# met_breadboard.net
KiCad netlist of a schematic drawn in Altium Designer
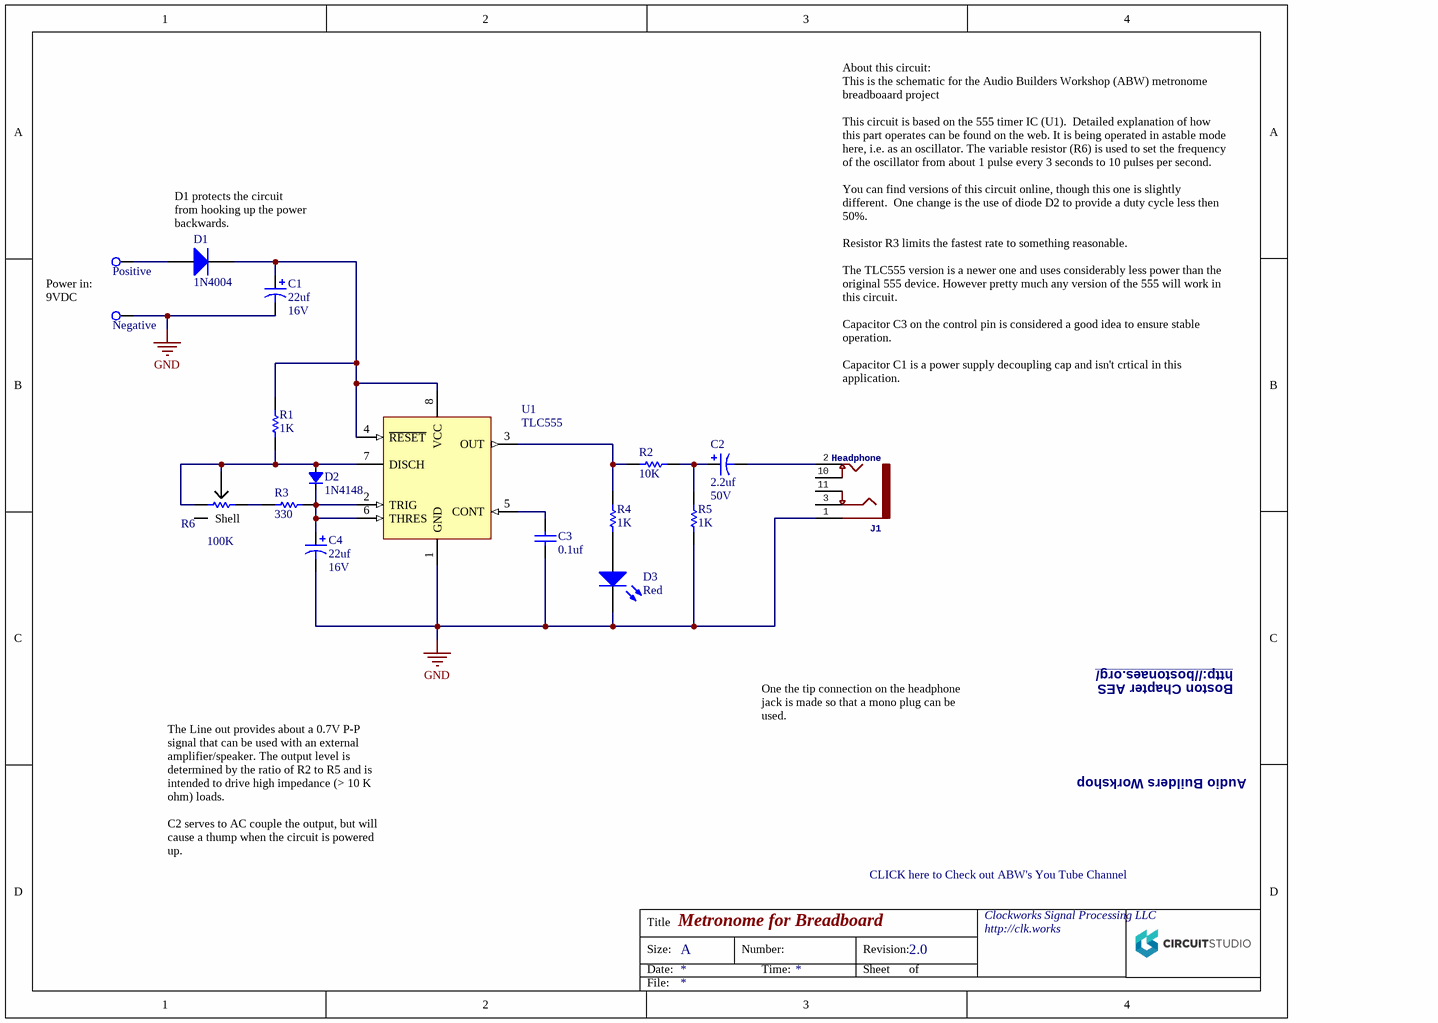
[diagram p0: met.breadboard.SchDoc]

(export (version "E")
  (design (tool "Eeschema 10.0.6"))
  (components
    (comp (ref "C1")
      (value "22uf")
      (footprint "SL Radial cap 2mm. 5Dx11.2mm")
      (description "22 uF 16V radial 85C 5x12 mm")
      (fields (field (name "VOLTAGE") "16V"))
      (libsource (lib "met") (part "SL-C0018-A"))
    )
    (comp (ref "C2")
      (value "2.2uf")
      (footprint "SL Radial cap 2mm. 5Dx11.2mm Brown")
      (description "2.2 uF 50V radial 85C 5x11mm")
      (fields (field (name "VOLTAGE") "50V"))
      (libsource (lib "met") (part "SL-C0020-A"))
    )
    (comp (ref "C3")
      (value "0.1uf")
      (footprint "SL 3.8mm TH 5.1mm lead space")
      (description ".1 uF TH .2\" lead")
      (fields (field (name "VOLTAGE") "50V"))
      (libsource (lib "met") (part "SL-C0019-A"))
    )
    (comp (ref "C4")
      (value "22uf")
      (footprint "SL Radial cap 2mm. 5Dx11.2mm")
      (description "22 uF 16V radial 85C 5x12 mm")
      (fields (field (name "VOLTAGE") "16V"))
      (libsource (lib "met") (part "SL-C0018-A"))
    )
    (comp (ref "D1")
      (value "1N4004")
      (footprint "SL DO-41")
      (description "1 Amp TH General Purpose Rectifier 400V")
      (fields (field (name "PUBLISHER") "Altium Limited"))
      (libsource (lib "met") (part "SL-D0004-A"))
    )
    (comp (ref "D2")
      (value "1N4148")
      (footprint "SL DO-35")
      (description "100 mA TH General Purpose Diode")
      (libsource (lib "met") (part "SL-D0005-A"))
    )
    (comp (ref "D3")
      (value "Red")
      (footprint "SL Green T13/4 LED")
      (description "Green T1 3/4 clear lens LED")
      (fields (field (name "Comment") "SL-D0006-A"))
      (libsource (lib "met") (part "SL-D0006-A"))
    )
    (comp (ref "J1")
      (value "Headphone")
      (footprint "SWITCHCRAFT_35RAPC4BHN2")
      (description "Conn 3.5MM Stereo Jack F 5 POS Solder RA Thru-Hole 5 Terminal 1 Port")
      (libsource (lib "CSP.J.connectors") (part "CSP-J0022-A"))
    )
    (comp (ref "R1")
      (value "1K")
      (footprint "SL Axial 1k 1/4W")
      (description "1K 1/4W TH")
      (libsource (lib "met") (part "SL-R0016-A"))
    )
    (comp (ref "R2")
      (value "10K")
      (footprint "SL Axial 10k 1/4W")
      (description "10K 1/4W TH")
      (libsource (lib "met") (part "SL-R0020-A"))
    )
    (comp (ref "R3")
      (value "330")
      (footprint "SL Axial 330 1/4W")
      (description "330 1/4W TH")
      (libsource (lib "met") (part "SL-R0019-A"))
    )
    (comp (ref "R4")
      (value "1K")
      (footprint "SL Axial 1k 1/4W")
      (description "1K 1/4W TH")
      (libsource (lib "met") (part "SL-R0016-A"))
    )
    (comp (ref "R5")
      (value "1K")
      (footprint "SL Axial 1k 1/4W")
      (description "1K 1/4W TH")
      (libsource (lib "met") (part "SL-R0016-A"))
    )
    (comp (ref "R6")
      (value "100K")
      (footprint "SL 9MM POT")
      (description "50 mW 9mm PCB mount linear taper pot")
      (libsource (lib "met") (part "SL-RV0001-A"))
    )
    (comp (ref "TP1")
      (value "Positive")
      (footprint "SL TEST POINT")
      (description "Connection point")
      (libsource (lib "met") (part "SL-X0005-A"))
    )
    (comp (ref "TP2")
      (value "Negative")
      (footprint "SL TEST POINT")
      (description "Connection point")
      (libsource (lib "met") (part "SL-X0005-A"))
    )
    (comp (ref "U1")
      (value "TLC555")
      (footprint "SL P0008A")
      (description "555 Timer 8 pin DIP, low power version")
      (libsource (lib "met") (part "SL-U0007-A"))
    )
  )
  (nets
    (net (code "1") (name "GND") (class "Default")
      (node (ref "C1") (pin "2") (pinfunction "2_2") (pintype "passive"))
      (node (ref "C3") (pin "1") (pinfunction "1_1") (pintype "passive"))
      (node (ref "C4") (pin "2") (pinfunction "2_2") (pintype "passive"))
      (node (ref "D3") (pin "2") (pinfunction "K_2") (pintype "passive"))
      (node (ref "J1") (pin "1") (pinfunction "SLEEVE_1") (pintype "passive"))
      (node (ref "R5") (pin "1") (pinfunction "1_1") (pintype "passive"))
      (node (ref "TP2") (pin "1") (pinfunction "TP_1") (pintype "passive"))
      (node (ref "U1") (pin "1") (pinfunction "GND_1") (pintype "power_in"))
    )
    (net (code "2") (name "Net-(C2-Pad1)") (class "Default")
      (node (ref "C2") (pin "1") (pinfunction "1_1") (pintype "passive"))
      (node (ref "R2") (pin "2") (pinfunction "2_2") (pintype "passive"))
      (node (ref "R5") (pin "2") (pinfunction "2_2") (pintype "passive"))
    )
    (net (code "3") (name "Net-(D1-A)") (class "Default")
      (node (ref "D1") (pin "1") (pinfunction "A_1") (pintype "passive"))
      (node (ref "TP1") (pin "1") (pinfunction "TP_1") (pintype "passive"))
    )
    (net (code "4") (name "Net-(D1-K)") (class "Default")
      (node (ref "C1") (pin "1") (pinfunction "1_1") (pintype "passive"))
      (node (ref "D1") (pin "2") (pinfunction "K_2") (pintype "passive"))
      (node (ref "R1") (pin "2") (pinfunction "2_2") (pintype "passive"))
      (node (ref "U1") (pin "4") (pinfunction "~{RESET}_4") (pintype "input"))
      (node (ref "U1") (pin "8") (pinfunction "VCC_8") (pintype "power_in"))
    )
    (net (code "5") (name "Net-(D2-A)") (class "Default")
      (node (ref "D2") (pin "1") (pinfunction "A_1") (pintype "passive"))
      (node (ref "R1") (pin "1") (pinfunction "1_1") (pintype "passive"))
      (node (ref "R6") (pin "1") (pinfunction "1_1") (pintype "passive"))
      (node (ref "R6") (pin "2") (pinfunction "2_2") (pintype "passive"))
      (node (ref "U1") (pin "7") (pinfunction "DISCH_7") (pintype "open_collector"))
    )
    (net (code "6") (name "Net-(D2-K)") (class "Default")
      (node (ref "C4") (pin "1") (pinfunction "1_1") (pintype "passive"))
      (node (ref "D2") (pin "2") (pinfunction "K_2") (pintype "passive"))
      (node (ref "R3") (pin "2") (pinfunction "2_2") (pintype "passive"))
      (node (ref "U1") (pin "2") (pinfunction "TRIG_2") (pintype "input"))
      (node (ref "U1") (pin "6") (pinfunction "THRES_6") (pintype "input"))
    )
    (net (code "7") (name "Net-(D3-A)") (class "Default")
      (node (ref "D3") (pin "1") (pinfunction "A_1") (pintype "passive"))
      (node (ref "R4") (pin "1") (pinfunction "1_1") (pintype "passive"))
    )
    (net (code "8") (name "Net-(J1-TIP)") (class "Default")
      (node (ref "C2") (pin "2") (pinfunction "2_2") (pintype "passive"))
      (node (ref "J1") (pin "2") (pinfunction "TIP_2") (pintype "passive"))
    )
    (net (code "9") (name "Net-(R3-Pad1)") (class "Default")
      (node (ref "R3") (pin "1") (pinfunction "1_1") (pintype "passive"))
      (node (ref "R6") (pin "3") (pinfunction "3_3") (pintype "passive"))
    )
    (net (code "10") (name "Net-(U1-CONT)") (class "Default")
      (node (ref "C3") (pin "2") (pinfunction "2_2") (pintype "passive"))
      (node (ref "U1") (pin "5") (pinfunction "CONT_5") (pintype "input"))
    )
    (net (code "11") (name "Net-(U1-OUT)") (class "Default")
      (node (ref "R2") (pin "1") (pinfunction "1_1") (pintype "passive"))
      (node (ref "R4") (pin "2") (pinfunction "2_2") (pintype "passive"))
      (node (ref "U1") (pin "3") (pinfunction "OUT_3") (pintype "output"))
    )
    (net (code "12") (name "unconnected-(J1-RING-Pad3)") (class "Default")
      (node (ref "J1") (pin "3") (pinfunction "RING_3") (pintype "passive"))
    )
    (net (code "13") (name "unconnected-(J1-RSH-Pad11)") (class "Default")
      (node (ref "J1") (pin "11") (pinfunction "RSH_11") (pintype "passive"))
    )
    (net (code "14") (name "unconnected-(J1-TSH-Pad10)") (class "Default")
      (node (ref "J1") (pin "10") (pinfunction "TSH_10") (pintype "passive"))
    )
    (net (code "15") (name "unconnected-(R6-Shell-Pad0)") (class "Default")
      (node (ref "R6") (pin "0") (pinfunction "Shell_0") (pintype "passive"))
    )
  )
)
